# HandHeld_Terminal_V2_Rev2.net
KiCad netlist of a schematic drawn in Altium Designer
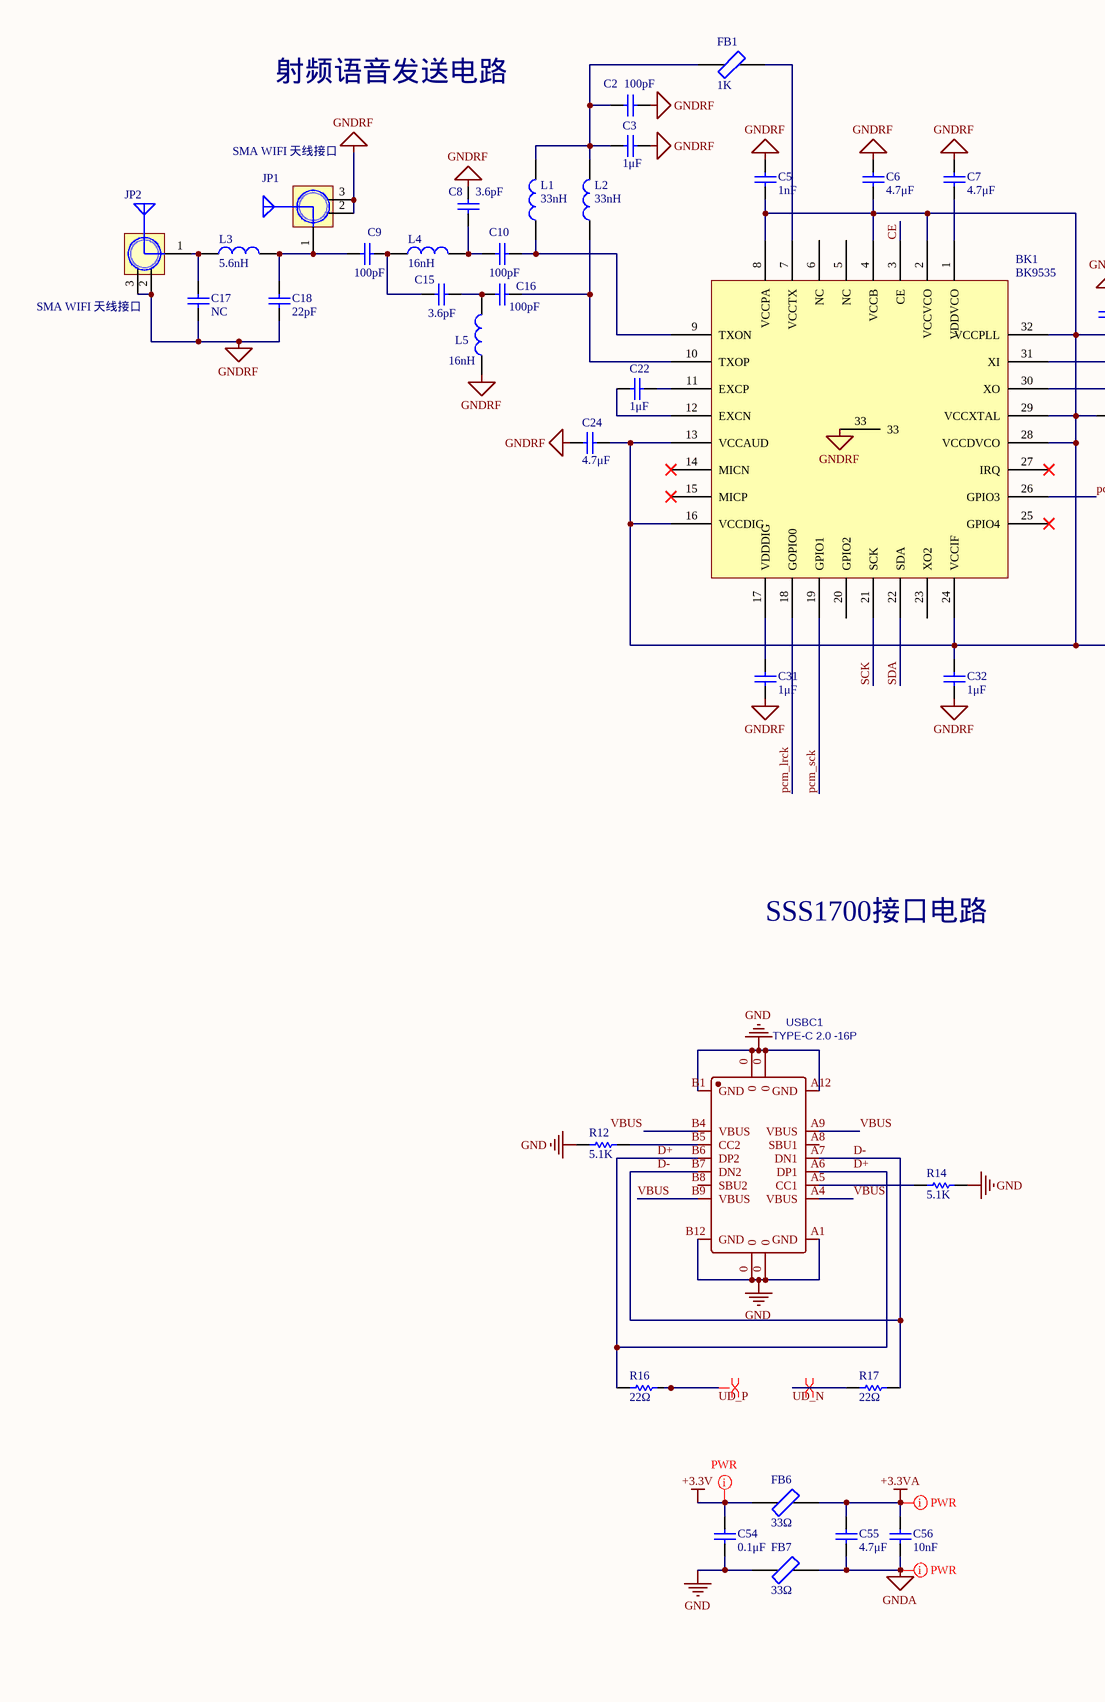
[diagram p0: HandHeld_Terminal_V2_Rev2.SchDoc, left]
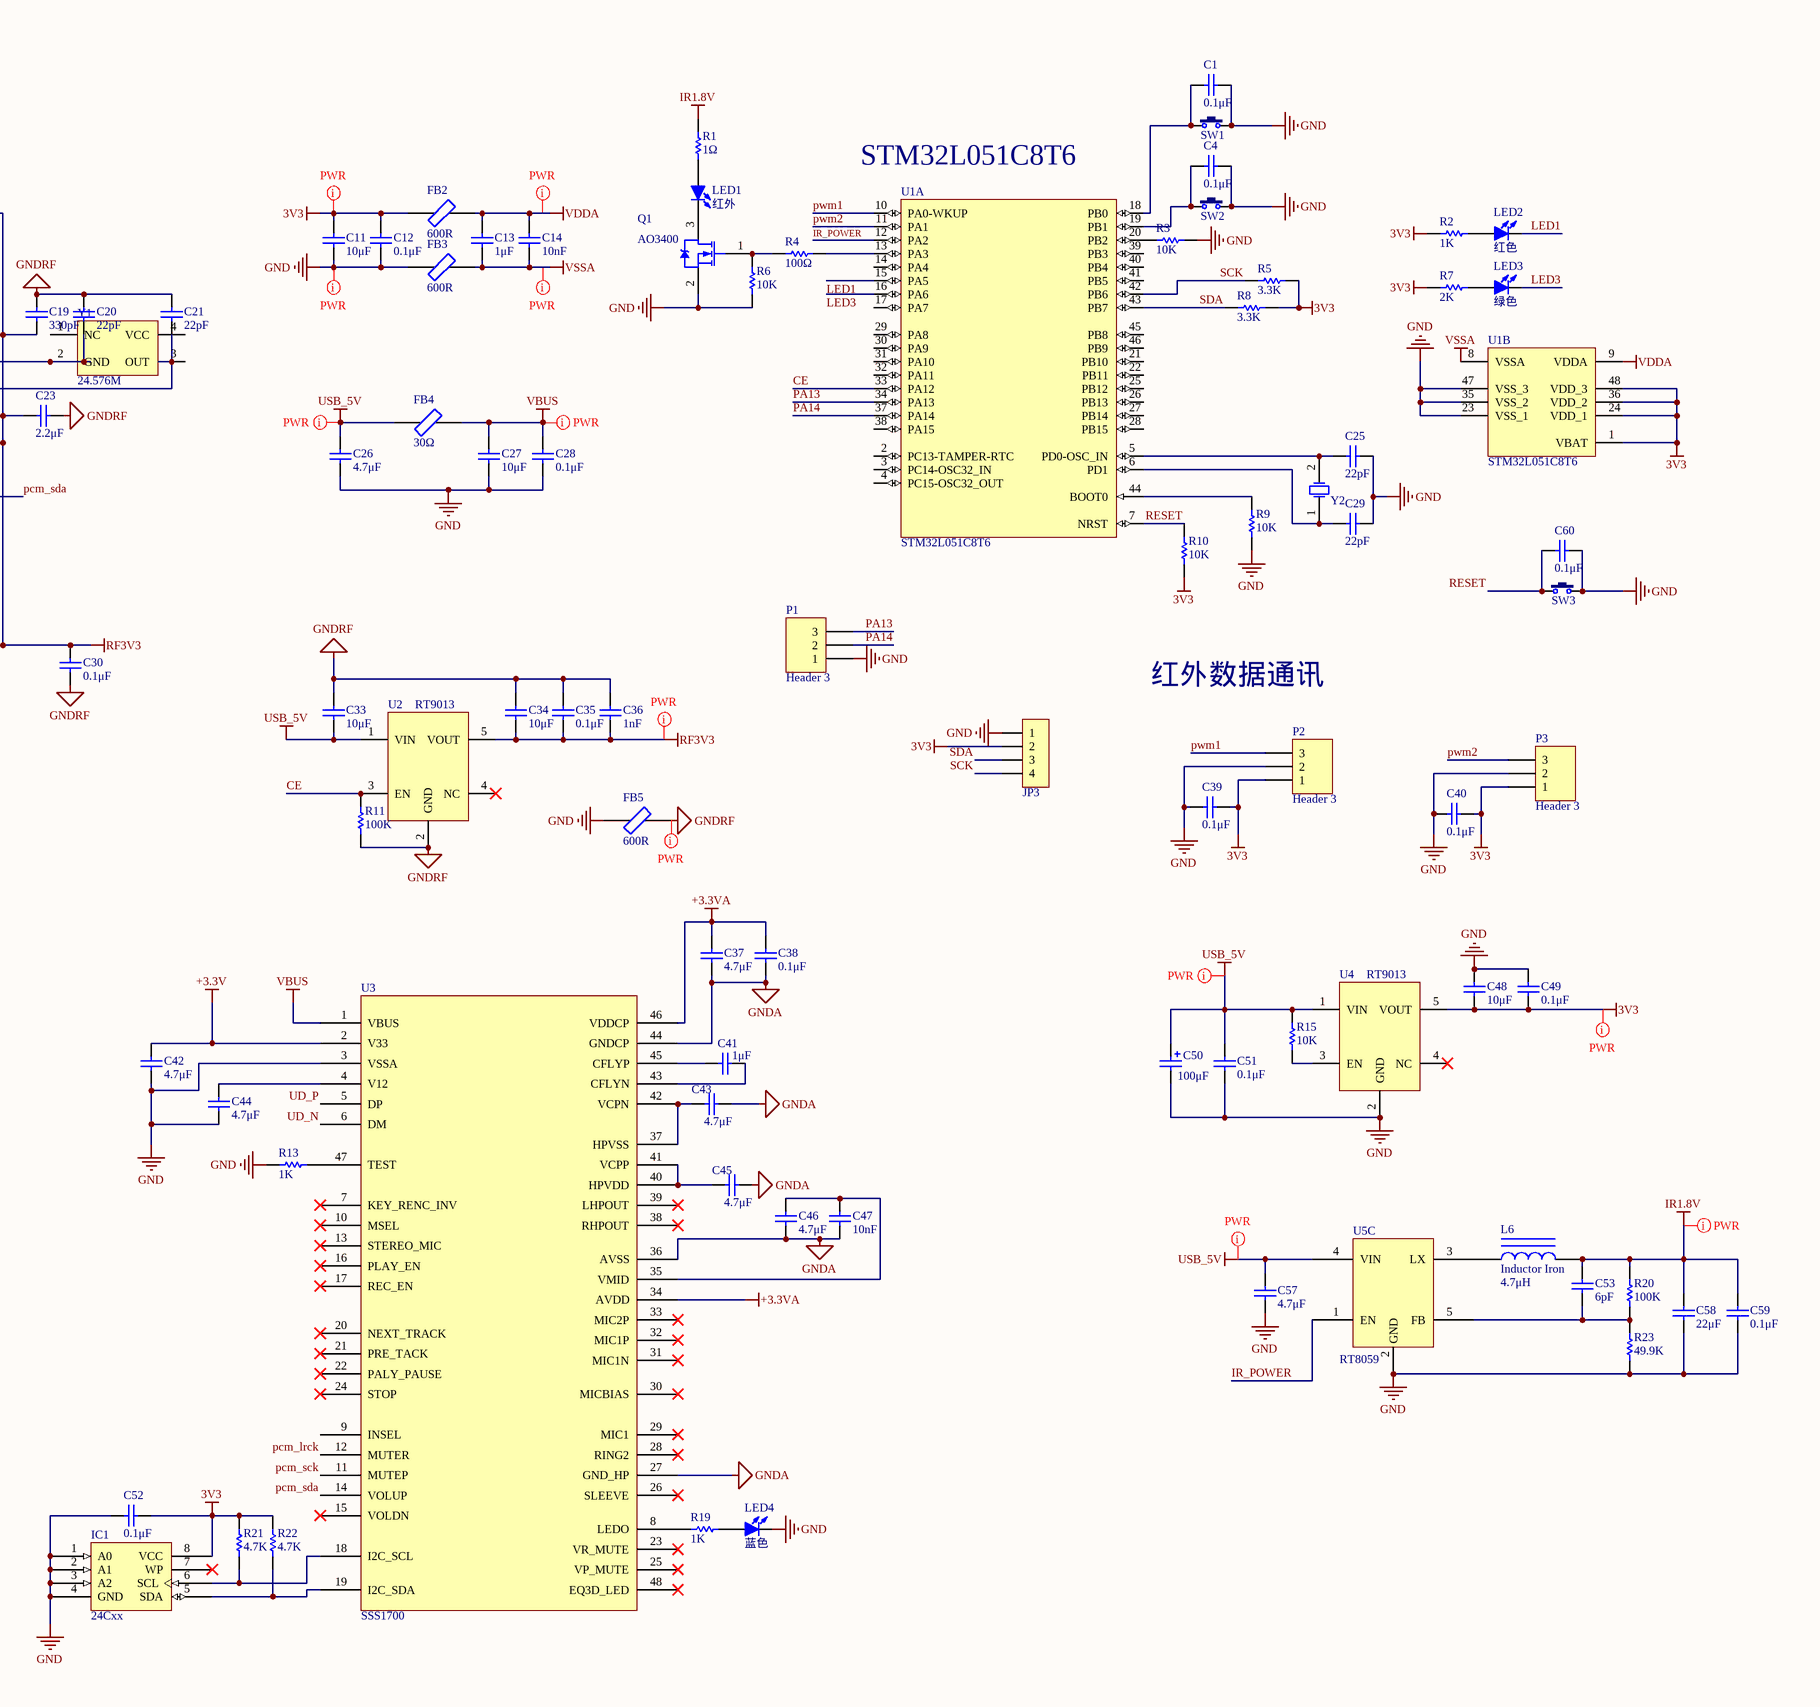
[diagram p1: HandHeld_Terminal_V2_Rev2.SchDoc, right]

(export (version "E")
  (design (tool "Eeschema 10.0.6"))
  (components
    (comp (ref "BK1") (value "BK9535") (footprint "QFN32 5x5_N") (libsource (lib "Nixie") (part "BK9530")))
    (comp (ref "C1")
      (value "0.1μF")
      (footprint "C 0603_L")
      (description "Capacitor")
      (fields (field (name "Comment") "Cap") (field (name "PUBLISHER") "Altium Limited"))
      (libsource (lib "Nixie") (part "Cap"))
    )
    (comp (ref "C2")
      (value "100pF")
      (footprint "C 0603_L")
      (description "Capacitor")
      (fields (field (name "Comment") "Cap") (field (name "PUBLISHER") "Altium Limited"))
      (libsource (lib "Nixie") (part "Cap"))
    )
    (comp (ref "C3")
      (value "1μF")
      (footprint "C 0603_L")
      (description "Capacitor")
      (fields (field (name "Comment") "Cap") (field (name "PUBLISHER") "Altium Limited"))
      (libsource (lib "Nixie") (part "Cap"))
    )
    (comp (ref "C4")
      (value "0.1μF")
      (footprint "C 0603_L")
      (description "Capacitor")
      (fields (field (name "Comment") "Cap") (field (name "PUBLISHER") "Altium Limited"))
      (libsource (lib "Nixie") (part "Cap"))
    )
    (comp (ref "C5")
      (value "1nF")
      (footprint "C 0603_L")
      (description "Capacitor")
      (fields (field (name "Comment") "Cap") (field (name "PUBLISHER") "Altium Limited"))
      (libsource (lib "Nixie") (part "Cap"))
    )
    (comp (ref "C6")
      (value "4.7μF")
      (footprint "C 0603_L")
      (description "Capacitor")
      (fields (field (name "Comment") "Cap") (field (name "PUBLISHER") "Altium Limited"))
      (libsource (lib "Nixie") (part "Cap"))
    )
    (comp (ref "C7")
      (value "4.7μF")
      (footprint "C 0603_L")
      (description "Capacitor")
      (fields (field (name "Comment") "Cap") (field (name "PUBLISHER") "Altium Limited"))
      (libsource (lib "Nixie") (part "Cap"))
    )
    (comp (ref "C8")
      (value "3.6pF")
      (footprint "C 0603_L")
      (description "Capacitor")
      (fields (field (name "Comment") "Cap") (field (name "PUBLISHER") "Altium Limited"))
      (libsource (lib "Nixie") (part "Cap"))
    )
    (comp (ref "C9")
      (value "100pF")
      (footprint "C 0603_L")
      (description "Capacitor")
      (fields (field (name "Comment") "Cap") (field (name "PUBLISHER") "Altium Limited"))
      (libsource (lib "Nixie") (part "Cap"))
    )
    (comp (ref "C10")
      (value "100pF")
      (footprint "C 0603_L")
      (description "Capacitor")
      (fields (field (name "Comment") "Cap") (field (name "PUBLISHER") "Altium Limited"))
      (libsource (lib "Nixie") (part "Cap"))
    )
    (comp (ref "C11")
      (value "10μF")
      (footprint "C 0805_L")
      (description "Capacitor")
      (fields (field (name "Comment") "Cap") (field (name "PUBLISHER") "Altium Limited"))
      (libsource (lib "Nixie") (part "Cap"))
    )
    (comp (ref "C12")
      (value "0.1μF")
      (footprint "C 0603_L")
      (description "Capacitor")
      (fields (field (name "Comment") "Cap") (field (name "PUBLISHER") "Altium Limited"))
      (libsource (lib "Nixie") (part "Cap"))
    )
    (comp (ref "C13")
      (value "1μF")
      (footprint "C 0603_L")
      (description "Capacitor")
      (fields (field (name "Comment") "Cap") (field (name "PUBLISHER") "Altium Limited"))
      (libsource (lib "Nixie") (part "Cap"))
    )
    (comp (ref "C14")
      (value "10nF")
      (footprint "C 0603_L")
      (description "Capacitor")
      (fields (field (name "Comment") "Cap") (field (name "PUBLISHER") "Altium Limited"))
      (libsource (lib "Nixie") (part "Cap"))
    )
    (comp (ref "C15")
      (value "3.6pF")
      (footprint "C 0603_L")
      (description "Capacitor")
      (fields (field (name "Comment") "Cap") (field (name "PUBLISHER") "Altium Limited"))
      (libsource (lib "Nixie") (part "Cap"))
    )
    (comp (ref "C16")
      (value "100pF")
      (footprint "C 0603_L")
      (description "Capacitor")
      (fields (field (name "Comment") "Cap") (field (name "PUBLISHER") "Altium Limited"))
      (libsource (lib "Nixie") (part "Cap"))
    )
    (comp (ref "C17")
      (value "NC")
      (footprint "C 0603_L")
      (description "Capacitor")
      (fields (field (name "Comment") "Cap") (field (name "PUBLISHER") "Altium Limited"))
      (libsource (lib "Nixie") (part "Cap"))
    )
    (comp (ref "C18")
      (value "22pF")
      (footprint "C 0603_L")
      (description "Capacitor")
      (fields (field (name "Comment") "Cap") (field (name "PUBLISHER") "Altium Limited"))
      (libsource (lib "Nixie") (part "Cap"))
    )
    (comp (ref "C19")
      (value "330pF")
      (footprint "C 0603_L")
      (description "Capacitor")
      (fields (field (name "Comment") "Cap") (field (name "PUBLISHER") "Altium Limited"))
      (libsource (lib "Nixie") (part "Cap"))
    )
    (comp (ref "C20")
      (value "22pF")
      (footprint "C 0603_L")
      (description "Capacitor")
      (fields (field (name "Comment") "Cap") (field (name "PUBLISHER") "Altium Limited"))
      (libsource (lib "Nixie") (part "Cap"))
    )
    (comp (ref "C21")
      (value "22pF")
      (footprint "C 0603_L")
      (description "Capacitor")
      (fields (field (name "Comment") "Cap") (field (name "PUBLISHER") "Altium Limited"))
      (libsource (lib "Nixie") (part "Cap"))
    )
    (comp (ref "C22")
      (value "1μF")
      (footprint "C 0603_L")
      (description "Capacitor")
      (fields (field (name "Comment") "Cap") (field (name "PUBLISHER") "Altium Limited"))
      (libsource (lib "Nixie") (part "Cap"))
    )
    (comp (ref "C23")
      (value "2.2μF")
      (footprint "C 0603_L")
      (description "Capacitor")
      (fields (field (name "Comment") "Cap") (field (name "PUBLISHER") "Altium Limited"))
      (libsource (lib "Nixie") (part "Cap"))
    )
    (comp (ref "C24")
      (value "4.7μF")
      (footprint "C 0603_L")
      (description "Capacitor")
      (fields (field (name "Comment") "Cap") (field (name "PUBLISHER") "Altium Limited"))
      (libsource (lib "Nixie") (part "Cap"))
    )
    (comp (ref "C25")
      (value "22pF")
      (footprint "C 0603_L")
      (description "Capacitor")
      (fields (field (name "Comment") "Cap") (field (name "PUBLISHER") "Altium Limited"))
      (libsource (lib "Nixie") (part "Cap"))
    )
    (comp (ref "C26")
      (value "4.7μF")
      (footprint "C 0805_L")
      (description "Capacitor")
      (fields (field (name "Comment") "Cap") (field (name "PUBLISHER") "Altium Limited"))
      (libsource (lib "Nixie") (part "Cap"))
    )
    (comp (ref "C27")
      (value "10μF")
      (footprint "C 0805_L")
      (description "Capacitor")
      (fields (field (name "Comment") "Cap") (field (name "PUBLISHER") "Altium Limited"))
      (libsource (lib "Nixie") (part "Cap"))
    )
    (comp (ref "C28")
      (value "0.1μF")
      (footprint "C 0603_L")
      (description "Capacitor")
      (fields (field (name "Comment") "Cap") (field (name "PUBLISHER") "Altium Limited"))
      (libsource (lib "Nixie") (part "Cap"))
    )
    (comp (ref "C29")
      (value "22pF")
      (footprint "C 0603_L")
      (description "Capacitor")
      (fields (field (name "Comment") "Cap") (field (name "PUBLISHER") "Altium Limited"))
      (libsource (lib "Nixie") (part "Cap"))
    )
    (comp (ref "C30")
      (value "0.1μF")
      (footprint "C 0603_L")
      (description "Capacitor")
      (fields (field (name "Comment") "Cap") (field (name "PUBLISHER") "Altium Limited"))
      (libsource (lib "Nixie") (part "Cap"))
    )
    (comp (ref "C31")
      (value "1μF")
      (footprint "C 0603_L")
      (description "Capacitor")
      (fields (field (name "Comment") "Cap") (field (name "PUBLISHER") "Altium Limited"))
      (libsource (lib "Nixie") (part "Cap"))
    )
    (comp (ref "C32")
      (value "1μF")
      (footprint "C 0603_L")
      (description "Capacitor")
      (fields (field (name "Comment") "Cap") (field (name "PUBLISHER") "Altium Limited"))
      (libsource (lib "Nixie") (part "Cap"))
    )
    (comp (ref "C33")
      (value "10μF")
      (footprint "C 0805_L")
      (description "Capacitor")
      (fields (field (name "Comment") "Cap") (field (name "PUBLISHER") "Altium Limited"))
      (libsource (lib "Nixie") (part "Cap"))
    )
    (comp (ref "C34")
      (value "10μF")
      (footprint "C 0805_L")
      (description "Capacitor")
      (fields (field (name "Comment") "Cap") (field (name "PUBLISHER") "Altium Limited"))
      (libsource (lib "Nixie") (part "Cap"))
    )
    (comp (ref "C35")
      (value "0.1μF")
      (footprint "C 0603_L")
      (description "Capacitor")
      (fields (field (name "Comment") "Cap") (field (name "PUBLISHER") "Altium Limited"))
      (libsource (lib "Nixie") (part "Cap"))
    )
    (comp (ref "C36")
      (value "1nF")
      (footprint "C 0603_L")
      (description "Capacitor")
      (fields (field (name "Comment") "Cap") (field (name "PUBLISHER") "Altium Limited"))
      (libsource (lib "Nixie") (part "Cap"))
    )
    (comp (ref "C37")
      (value "4.7μF")
      (footprint "C 0603_L")
      (description "Capacitor")
      (fields (field (name "Comment") "Cap") (field (name "PUBLISHER") "Altium Limited"))
      (libsource (lib "Nixie") (part "Cap"))
    )
    (comp (ref "C38")
      (value "0.1μF")
      (footprint "C 0603_L")
      (description "Capacitor")
      (fields (field (name "Comment") "Cap") (field (name "PUBLISHER") "Altium Limited"))
      (libsource (lib "Nixie") (part "Cap"))
    )
    (comp (ref "C39")
      (value "0.1μF")
      (footprint "C 0603_L")
      (description "Capacitor")
      (fields (field (name "Comment") "Cap") (field (name "PUBLISHER") "Altium Limited"))
      (libsource (lib "Nixie") (part "Cap"))
    )
    (comp (ref "C40")
      (value "0.1μF")
      (footprint "C 0603_L")
      (description "Capacitor")
      (fields (field (name "Comment") "Cap") (field (name "PUBLISHER") "Altium Limited"))
      (libsource (lib "Nixie") (part "Cap"))
    )
    (comp (ref "C41")
      (value "1μF")
      (footprint "C 0603_L")
      (description "Capacitor")
      (fields (field (name "Comment") "Cap") (field (name "PUBLISHER") "Altium Limited"))
      (libsource (lib "Nixie") (part "Cap"))
    )
    (comp (ref "C42")
      (value "4.7μF")
      (footprint "C 0603_L")
      (description "Capacitor")
      (fields (field (name "Comment") "Cap") (field (name "PUBLISHER") "Altium Limited"))
      (libsource (lib "Nixie") (part "Cap"))
    )
    (comp (ref "C43")
      (value "4.7μF")
      (footprint "C 0603_L")
      (description "Capacitor")
      (fields (field (name "Comment") "Cap") (field (name "PUBLISHER") "Altium Limited"))
      (libsource (lib "Nixie") (part "Cap"))
    )
    (comp (ref "C44")
      (value "4.7μF")
      (footprint "C 0603_L")
      (description "Capacitor")
      (fields (field (name "Comment") "Cap") (field (name "PUBLISHER") "Altium Limited"))
      (libsource (lib "Nixie") (part "Cap"))
    )
    (comp (ref "C45")
      (value "4.7μF")
      (footprint "C 0603_L")
      (description "Capacitor")
      (fields (field (name "Comment") "Cap") (field (name "PUBLISHER") "Altium Limited"))
      (libsource (lib "Nixie") (part "Cap"))
    )
    (comp (ref "C46")
      (value "4.7μF")
      (footprint "C 0603_L")
      (description "Capacitor")
      (fields (field (name "Comment") "Cap") (field (name "PUBLISHER") "Altium Limited"))
      (libsource (lib "Nixie") (part "Cap"))
    )
    (comp (ref "C47")
      (value "10nF")
      (footprint "C 0603_L")
      (description "Capacitor")
      (fields (field (name "Comment") "Cap") (field (name "PUBLISHER") "Altium Limited"))
      (libsource (lib "Nixie") (part "Cap"))
    )
    (comp (ref "C48")
      (value "10μF")
      (footprint "C 0805_L")
      (description "Capacitor")
      (fields (field (name "Comment") "Cap") (field (name "PUBLISHER") "Altium Limited"))
      (libsource (lib "Nixie") (part "Cap"))
    )
    (comp (ref "C49")
      (value "0.1μF")
      (footprint "C 0603_L")
      (description "Capacitor")
      (fields (field (name "Comment") "Cap") (field (name "PUBLISHER") "Altium Limited"))
      (libsource (lib "Nixie") (part "Cap"))
    )
    (comp (ref "C50")
      (value "100μF")
      (footprint "CM C(5*5.4)")
      (description "Polarized Capacitor (Radial)")
      (fields (field (name "Comment") "Cap Pol1") (field (name "PUBLISHER") "Altium Limited"))
      (libsource (lib "Nixie") (part "Cap Pol1"))
    )
    (comp (ref "C51")
      (value "0.1μF")
      (footprint "C 0603_L")
      (description "Capacitor")
      (fields (field (name "Comment") "Cap") (field (name "PUBLISHER") "Altium Limited"))
      (libsource (lib "Nixie") (part "Cap"))
    )
    (comp (ref "C52")
      (value "0.1μF")
      (footprint "C 0603_L")
      (description "Capacitor")
      (fields (field (name "Comment") "Cap") (field (name "PUBLISHER") "Altium Limited"))
      (libsource (lib "Nixie") (part "Cap"))
    )
    (comp (ref "C53")
      (value "6pF")
      (footprint "C 0603_L")
      (description "Capacitor")
      (fields (field (name "Comment") "Cap") (field (name "PUBLISHER") "Altium Limited"))
      (libsource (lib "Nixie") (part "Cap"))
    )
    (comp (ref "C54")
      (value "0.1μF")
      (footprint "C 0603_L")
      (description "Capacitor")
      (fields (field (name "Comment") "Cap") (field (name "PUBLISHER") "Altium Limited"))
      (libsource (lib "Nixie") (part "Cap"))
    )
    (comp (ref "C55")
      (value "4.7μF")
      (footprint "C 0805_L")
      (description "Capacitor")
      (fields (field (name "Comment") "Cap") (field (name "PUBLISHER") "Altium Limited"))
      (libsource (lib "Nixie") (part "Cap"))
    )
    (comp (ref "C56")
      (value "10nF")
      (footprint "C 0603_L")
      (description "Capacitor")
      (fields (field (name "Comment") "Cap") (field (name "PUBLISHER") "Altium Limited"))
      (libsource (lib "Nixie") (part "Cap"))
    )
    (comp (ref "C57")
      (value "4.7μF")
      (footprint "C 0603_L")
      (description "Capacitor")
      (fields (field (name "Comment") "Cap") (field (name "PUBLISHER") "Altium Limited"))
      (libsource (lib "Nixie") (part "Cap"))
    )
    (comp (ref "C58")
      (value "22μF")
      (footprint "C 0805_L")
      (description "Capacitor")
      (fields (field (name "Comment") "Cap") (field (name "PUBLISHER") "Altium Limited"))
      (libsource (lib "Nixie") (part "Cap"))
    )
    (comp (ref "C59")
      (value "0.1μF")
      (footprint "C 0603_L")
      (description "Capacitor")
      (fields (field (name "Comment") "Cap") (field (name "PUBLISHER") "Altium Limited"))
      (libsource (lib "Nixie") (part "Cap"))
    )
    (comp (ref "C60")
      (value "0.1μF")
      (footprint "C 0603_L")
      (description "Capacitor")
      (fields (field (name "Comment") "Cap") (field (name "PUBLISHER") "Altium Limited"))
      (libsource (lib "Nixie") (part "Cap"))
    )
    (comp (ref "FB1")
      (value "1K")
      (footprint "C 0603_L")
      (description "铁氧体磁珠")
      (fields (field (name "Comment") "Ferrite bead"))
      (libsource (lib "Nixie") (part "Ferrite bead"))
    )
    (comp (ref "FB2")
      (value "600R")
      (footprint "C 0603_L")
      (description "铁氧体磁珠")
      (fields (field (name "Comment") "Ferrite bead"))
      (libsource (lib "Nixie") (part "Ferrite bead"))
    )
    (comp (ref "FB3")
      (value "600R")
      (footprint "C 0603_L")
      (description "铁氧体磁珠")
      (fields (field (name "Comment") "Ferrite bead"))
      (libsource (lib "Nixie") (part "Ferrite bead"))
    )
    (comp (ref "FB4")
      (value "30Ω")
      (footprint "C 0603_L")
      (description "铁氧体磁珠")
      (fields (field (name "Comment") "Ferrite bead"))
      (libsource (lib "Nixie") (part "Ferrite bead"))
    )
    (comp (ref "FB5")
      (value "600R")
      (footprint "C 0805_L")
      (description "铁氧体磁珠")
      (fields (field (name "Comment") "Ferrite bead"))
      (libsource (lib "Nixie") (part "Ferrite bead"))
    )
    (comp (ref "FB6")
      (value "33Ω")
      (footprint "C 0603_L")
      (description "铁氧体磁珠")
      (fields (field (name "Comment") "Ferrite bead"))
      (libsource (lib "Nixie") (part "Ferrite bead"))
    )
    (comp (ref "FB7")
      (value "33Ω")
      (footprint "C 0603_L")
      (description "铁氧体磁珠")
      (fields (field (name "Comment") "Ferrite bead"))
      (libsource (lib "Nixie") (part "Ferrite bead"))
    )
    (comp (ref "IC1")
      (value "24Cxx")
      (footprint "SOP8_L")
      (description "外置EEPROM")
      (fields (field (name "版权归属") "封装库来自淘宝 ID：黄晶宝石"))
      (libsource (lib "Nixie") (part "24Cxx"))
    )
    (comp (ref "JP1")
      (value "SMA WIFI 天线接口")
      (footprint "COAXIAL/SMD/CON/V/I-PEX/W08-5801")
      (description "SMA-2.4G射频天线接口")
      (fields (field (name "版权归属") "封装库来自淘宝 ID：黄晶宝石"))
      (libsource (lib "") (part "SMA_1"))
    )
    (comp (ref "JP2")
      (value "SMA WIFI 天线接口")
      (footprint "SMA-KE")
      (description "SMA-2.4G射频天线接口")
      (fields (field (name "版权归属") "封装库来自淘宝 ID：黄晶宝石"))
      (libsource (lib "Nixie") (part "SMA"))
    )
    (comp (ref "JP3")
      (value "HDR-1X4")
      (footprint "HDR2.54-LI-4P")
      (description "4P接插件")
      (fields (field (name "版权归属") "封装库来自淘宝 ID：黄晶宝石"))
      (libsource (lib "Nixie") (part "Header 4"))
    )
    (comp (ref "L1")
      (value "33nH")
      (footprint "L 0603")
      (description "小功率贴片电感")
      (fields (field (name "Comment") "L"))
      (libsource (lib "Nixie") (part "L"))
    )
    (comp (ref "L2")
      (value "33nH")
      (footprint "L 0603")
      (description "小功率贴片电感")
      (fields (field (name "Comment") "L"))
      (libsource (lib "Nixie") (part "L"))
    )
    (comp (ref "L3")
      (value "5.6nH")
      (footprint "L 0603")
      (description "小功率贴片电感")
      (fields (field (name "Comment") "L"))
      (libsource (lib "Nixie") (part "L"))
    )
    (comp (ref "L4")
      (value "16nH")
      (footprint "L 0603")
      (description "小功率贴片电感")
      (fields (field (name "Comment") "L"))
      (libsource (lib "Nixie") (part "L"))
    )
    (comp (ref "L5")
      (value "16nH")
      (footprint "L 0603")
      (description "小功率贴片电感")
      (fields (field (name "Comment") "L"))
      (libsource (lib "Nixie") (part "L"))
    )
    (comp (ref "L6")
      (value "Inductor Iron")
      (footprint "NR2520")
      (description "Magnetic-Core Inductor")
      (fields (field (name "ALTIUM_VALUE") "4.7μH") (field (name "PUBLISHER") "Altium Limited"))
      (libsource (lib "Nixie") (part "Inductor Iron"))
    )
    (comp (ref "LED1")
      (value "红外")
      (footprint "LED 1W/3W")
      (description "贴片LED")
      (fields (field (name "版权归属") "封装库来自淘宝 ID：黄晶宝石"))
      (libsource (lib "Nixie") (part "LED-SMD"))
    )
    (comp (ref "LED2")
      (value "红色")
      (footprint "LED 0805R")
      (description "贴片LED")
      (fields (field (name "版权归属") "封装库来自淘宝 ID：黄晶宝石"))
      (libsource (lib "Nixie") (part "LED-SMD"))
    )
    (comp (ref "LED3")
      (value "绿色")
      (footprint "LED 0805G")
      (description "贴片LED")
      (fields (field (name "版权归属") "封装库来自淘宝 ID：黄晶宝石"))
      (libsource (lib "Nixie") (part "LED-SMD"))
    )
    (comp (ref "LED4")
      (value "蓝色")
      (footprint "LED 0805B")
      (description "贴片LED")
      (fields (field (name "版权归属") "封装库来自淘宝 ID：黄晶宝石"))
      (libsource (lib "Nixie") (part "LED-SMD"))
    )
    (comp (ref "P1")
      (value "Header 3")
      (footprint "HDR2.54-LI-3P")
      (description "Header, 3-Pin")
      (fields (field (name "PUBLISHER") "Altium Limited"))
      (libsource (lib "Miscellaneous Connectors") (part "Header 3"))
    )
    (comp (ref "P2")
      (value "Header 3")
      (footprint "HDR1X3")
      (description "Header, 3-Pin")
      (fields (field (name "PUBLISHER") "Altium Limited"))
      (libsource (lib "") (part "Header 3_1"))
    )
    (comp (ref "P3")
      (value "Header 3")
      (footprint "HDR1X3")
      (description "Header, 3-Pin")
      (fields (field (name "PUBLISHER") "Altium Limited"))
      (libsource (lib "") (part "Header 3_1"))
    )
    (comp (ref "Q1")
      (value "AO3400")
      (footprint "SOT-23-3L")
      (description "N-Channel Power MOSFET")
      (fields (field (name "PUBLISHER") "Altium Limited"))
      (libsource (lib "Nixie") (part "NMOS-2"))
    )
    (comp (ref "R1")
      (value "1Ω")
      (footprint "R 0805_L")
      (description "Resistor")
      (fields (field (name "PUBLISHER") "Altium Limited"))
      (libsource (lib "Nixie") (part "Resistor"))
    )
    (comp (ref "R2")
      (value "1K")
      (footprint "R 0603_L")
      (description "Resistor")
      (fields (field (name "PUBLISHER") "Altium Limited"))
      (libsource (lib "Nixie") (part "Resistor"))
    )
    (comp (ref "R3")
      (value "10K")
      (footprint "R 0603_L")
      (description "Resistor")
      (fields (field (name "PUBLISHER") "Altium Limited"))
      (libsource (lib "Nixie") (part "Resistor"))
    )
    (comp (ref "R4")
      (value "100Ω")
      (footprint "R 0603_L")
      (description "Resistor")
      (fields (field (name "PUBLISHER") "Altium Limited"))
      (libsource (lib "Nixie") (part "Resistor"))
    )
    (comp (ref "R5")
      (value "3.3K")
      (footprint "R 0603_L")
      (description "Resistor")
      (fields (field (name "PUBLISHER") "Altium Limited"))
      (libsource (lib "Nixie") (part "Resistor"))
    )
    (comp (ref "R6")
      (value "10K")
      (footprint "R 0603_L")
      (description "Resistor")
      (fields (field (name "PUBLISHER") "Altium Limited"))
      (libsource (lib "Nixie") (part "Resistor"))
    )
    (comp (ref "R7")
      (value "2K")
      (footprint "R 0603_L")
      (description "Resistor")
      (fields (field (name "PUBLISHER") "Altium Limited"))
      (libsource (lib "Nixie") (part "Resistor"))
    )
    (comp (ref "R8")
      (value "3.3K")
      (footprint "R 0603_L")
      (description "Resistor")
      (fields (field (name "PUBLISHER") "Altium Limited"))
      (libsource (lib "Nixie") (part "Resistor"))
    )
    (comp (ref "R9")
      (value "10K")
      (footprint "R 0603_L")
      (description "Resistor")
      (fields (field (name "PUBLISHER") "Altium Limited"))
      (libsource (lib "Nixie") (part "Resistor"))
    )
    (comp (ref "R10")
      (value "10K")
      (footprint "R 0603_L")
      (description "Resistor")
      (fields (field (name "PUBLISHER") "Altium Limited"))
      (libsource (lib "Nixie") (part "Resistor"))
    )
    (comp (ref "R11")
      (value "100K")
      (footprint "R 0603_L")
      (description "Resistor")
      (fields (field (name "PUBLISHER") "Altium Limited"))
      (libsource (lib "Nixie") (part "Resistor"))
    )
    (comp (ref "R12")
      (value "5.1K")
      (footprint "R 0603_L")
      (description "Resistor")
      (fields (field (name "PUBLISHER") "Altium Limited"))
      (libsource (lib "Nixie") (part "Resistor"))
    )
    (comp (ref "R13")
      (value "1K")
      (footprint "R 0603_L")
      (description "Resistor")
      (fields (field (name "PUBLISHER") "Altium Limited"))
      (libsource (lib "Nixie") (part "Resistor"))
    )
    (comp (ref "R14")
      (value "5.1K")
      (footprint "R 0603_L")
      (description "Resistor")
      (fields (field (name "PUBLISHER") "Altium Limited"))
      (libsource (lib "Nixie") (part "Resistor"))
    )
    (comp (ref "R15")
      (value "10K")
      (footprint "R 0603_L")
      (description "Resistor")
      (fields (field (name "PUBLISHER") "Altium Limited"))
      (libsource (lib "Nixie") (part "Resistor"))
    )
    (comp (ref "R16")
      (value "22Ω")
      (footprint "R 0603_L")
      (description "Resistor")
      (fields (field (name "PUBLISHER") "Altium Limited"))
      (libsource (lib "Nixie") (part "Resistor"))
    )
    (comp (ref "R17")
      (value "22Ω")
      (footprint "R 0603_L")
      (description "Resistor")
      (fields (field (name "PUBLISHER") "Altium Limited"))
      (libsource (lib "Nixie") (part "Resistor"))
    )
    (comp (ref "R19")
      (value "1K")
      (footprint "R 0603_L")
      (description "Resistor")
      (fields (field (name "PUBLISHER") "Altium Limited"))
      (libsource (lib "Nixie") (part "Resistor"))
    )
    (comp (ref "R20")
      (value "100K")
      (footprint "R 0603_L")
      (description "Resistor")
      (fields (field (name "PUBLISHER") "Altium Limited"))
      (libsource (lib "Nixie") (part "Resistor"))
    )
    (comp (ref "R21")
      (value "4.7K")
      (footprint "R 0603_L")
      (description "Resistor")
      (fields (field (name "PUBLISHER") "Altium Limited"))
      (libsource (lib "Nixie") (part "Resistor"))
    )
    (comp (ref "R22")
      (value "4.7K")
      (footprint "R 0603_L")
      (description "Resistor")
      (fields (field (name "PUBLISHER") "Altium Limited"))
      (libsource (lib "Nixie") (part "Resistor"))
    )
    (comp (ref "R23")
      (value "49.9K")
      (footprint "R 0603_L")
      (description "Resistor")
      (fields (field (name "PUBLISHER") "Altium Limited"))
      (libsource (lib "Nixie") (part "Resistor"))
    )
    (comp (ref "SW1")
      (value "3x6x5")
      (footprint "TSW SMD-3*6*2.5")
      (description "3x6轻触开关")
      (fields (field (name "版权归属") "封装库来自淘宝 ID：黄晶宝石"))
      (libsource (lib "Nixie") (part "TSW 3x6"))
    )
    (comp (ref "SW2")
      (value "3x6x5")
      (footprint "TSW SMD-3*6*2.5")
      (description "3x6轻触开关")
      (fields (field (name "版权归属") "封装库来自淘宝 ID：黄晶宝石"))
      (libsource (lib "Nixie") (part "TSW 3x6"))
    )
    (comp (ref "SW3")
      (value "3x6x5")
      (footprint "TSW SMD-3*6*2.5")
      (description "3x6轻触开关")
      (fields (field (name "版权归属") "封装库来自淘宝 ID：黄晶宝石"))
      (libsource (lib "Nixie") (part "TSW 3x6"))
    )
    (comp (ref "U1")
      (value "STM32L051C8T6")
      (footprint "LQFP48_L")
      (description "ARM")
      (libsource (lib "") (part "STM32F103C8T6_1"))
    )
    (comp (ref "U2")
      (value "RT9013")
      (footprint "SOT23-5L")
      (description "LDO")
      (libsource (lib "HandHeld_terminal") (part "RT9013"))
    )
    (comp (ref "U3")
      (value "SSS1700")
      (footprint "LQFP48_L")
      (description "USB音频芯片")
      (libsource (lib "Nixie") (part "SSS1700"))
    )
    (comp (ref "U4")
      (value "RT9013")
      (footprint "SOT23-5L")
      (description "LDO")
      (libsource (lib "HandHeld_terminal") (part "RT9013"))
    )
    (comp (ref "U5")
      (value "RT8059")
      (footprint "SOT23-5L")
      (description "DC-DC, 2.8-5.5V,1A")
      (libsource (lib "Nixie") (part "RT8059"))
    )
    (comp (ref "USBC1")
      (value "TYPE-C 2.0 -16P")
      (footprint "USB-C-SMD_TYPE-C-USB-5")
      (description "USB2.0 Type-C 母座 16Pin")
      (libsource (lib "Nixie") (part "USB2.0 Type-C 16Pin母座"))
    )
    (comp (ref "Y1")
      (value "24.576M")
      (footprint "OSC 3225-4P")
      (description "4脚有源晶振")
      (libsource (lib "Nixie") (part "XTAL"))
    )
    (comp (ref "Y2")
      (value "8MHz ±20ppm 20pF")
      (footprint "OSC 5032-2P")
      (description "贴片晶振")
      (libsource (lib "HandHeld_terminal") (part "SMD-5032_2P 8MHz 20ppm 20pF"))
    )
  )
  (nets
    (net (code "1") (name "+3.3V") (class "Default")
      (node (ref "C42") (pin "2") (pinfunction "2_2") (pintype "passive"))
      (node (ref "C54") (pin "2") (pinfunction "2_2") (pintype "passive"))
      (node (ref "FB6") (pin "1") (pinfunction "1_1") (pintype "passive"))
      (node (ref "U3") (pin "2") (pinfunction "V33_2") (pintype "passive"))
    )
    (net (code "2") (name "+3.3VA") (class "Default")
      (node (ref "C37") (pin "2") (pinfunction "2_2") (pintype "passive"))
      (node (ref "C38") (pin "2") (pinfunction "2_2") (pintype "passive"))
      (node (ref "C55") (pin "2") (pinfunction "2_2") (pintype "passive"))
      (node (ref "C56") (pin "2") (pinfunction "2_2") (pintype "passive"))
      (node (ref "FB6") (pin "2") (pinfunction "2_2") (pintype "passive"))
      (node (ref "U3") (pin "34") (pinfunction "AVDD_34") (pintype "passive"))
      (node (ref "U3") (pin "46") (pinfunction "VDDCP_46") (pintype "passive"))
    )
    (net (code "3") (name "/CE") (class "Default")
      (node (ref "BK1") (pin "3") (pinfunction "CE_3") (pintype "passive"))
      (node (ref "R11") (pin "2") (pinfunction "2_2") (pintype "passive"))
      (node (ref "U1") (pin "33") (pinfunction "PA12_33") (pintype "bidirectional"))
      (node (ref "U2") (pin "3") (pinfunction "EN_3") (pintype "passive"))
    )
    (net (code "4") (name "/D+") (class "Default")
      (node (ref "R16") (pin "1") (pinfunction "1_1") (pintype "passive"))
      (node (ref "USBC1") (pin "A6") (pinfunction "DP1_A6") (pintype "passive"))
      (node (ref "USBC1") (pin "B6") (pinfunction "DP2_B6") (pintype "passive"))
    )
    (net (code "5") (name "/D-") (class "Default")
      (node (ref "R17") (pin "2") (pinfunction "2_2") (pintype "passive"))
      (node (ref "USBC1") (pin "A7") (pinfunction "DN1_A7") (pintype "passive"))
      (node (ref "USBC1") (pin "B7") (pinfunction "DN2_B7") (pintype "passive"))
    )
    (net (code "6") (name "/IR_POWER") (class "Default")
      (node (ref "U1") (pin "12") (pinfunction "PA2_12") (pintype "bidirectional"))
      (node (ref "U5") (pin "1") (pinfunction "EN_1") (pintype "passive"))
    )
    (net (code "7") (name "/LED1") (class "Default")
      (node (ref "LED2") (pin "2") (pinfunction "K_2") (pintype "passive"))
      (node (ref "U1") (pin "15") (pinfunction "PA5_15") (pintype "bidirectional"))
    )
    (net (code "8") (name "/LED3") (class "Default")
      (node (ref "LED3") (pin "2") (pinfunction "K_2") (pintype "passive"))
      (node (ref "U1") (pin "16") (pinfunction "PA6_16") (pintype "bidirectional"))
    )
    (net (code "9") (name "/PA13") (class "Default")
      (node (ref "P1") (pin "3") (pinfunction "3_3") (pintype "passive"))
      (node (ref "U1") (pin "34") (pinfunction "PA13_34") (pintype "bidirectional"))
    )
    (net (code "10") (name "/PA14") (class "Default")
      (node (ref "P1") (pin "2") (pinfunction "2_2") (pintype "passive"))
      (node (ref "U1") (pin "37") (pinfunction "PA14_37") (pintype "bidirectional"))
    )
    (net (code "11") (name "/RESET") (class "Default")
      (node (ref "C60") (pin "2") (pinfunction "2_2") (pintype "passive"))
      (node (ref "R10") (pin "1") (pinfunction "1_1") (pintype "passive"))
      (node (ref "SW3") (pin "1") (pinfunction "1_1") (pintype "passive"))
      (node (ref "U1") (pin "7") (pinfunction "NRST_7") (pintype "bidirectional"))
    )
    (net (code "12") (name "/SCK") (class "Default")
      (node (ref "BK1") (pin "21") (pinfunction "SCK_21") (pintype "passive"))
      (node (ref "JP3") (pin "4") (pinfunction "4_4") (pintype "passive"))
      (node (ref "R5") (pin "2") (pinfunction "2_2") (pintype "passive"))
      (node (ref "U1") (pin "42") (pinfunction "PB6_42") (pintype "bidirectional"))
    )
    (net (code "13") (name "/SDA") (class "Default")
      (node (ref "BK1") (pin "22") (pinfunction "SDA_22") (pintype "passive"))
      (node (ref "JP3") (pin "3") (pinfunction "3_3") (pintype "passive"))
      (node (ref "R8") (pin "2") (pinfunction "2_2") (pintype "passive"))
      (node (ref "U1") (pin "43") (pinfunction "PB7_43") (pintype "bidirectional"))
    )
    (net (code "14") (name "/UD_N") (class "Default")
      (node (ref "R17") (pin "1") (pinfunction "1_1") (pintype "passive"))
      (node (ref "U3") (pin "6") (pinfunction "DM_6") (pintype "passive"))
    )
    (net (code "15") (name "/UD_P") (class "Default")
      (node (ref "R16") (pin "2") (pinfunction "2_2") (pintype "passive"))
      (node (ref "U3") (pin "5") (pinfunction "DP_5") (pintype "passive"))
    )
    (net (code "16") (name "/pcm_lrck") (class "Default")
      (node (ref "BK1") (pin "18") (pinfunction "GOPIO0_18") (pintype "passive"))
      (node (ref "U3") (pin "12") (pinfunction "MUTER_12") (pintype "passive"))
    )
    (net (code "17") (name "/pcm_sck") (class "Default")
      (node (ref "BK1") (pin "19") (pinfunction "GPIO1_19") (pintype "passive"))
      (node (ref "U3") (pin "11") (pinfunction "MUTEP_11") (pintype "passive"))
    )
    (net (code "18") (name "/pcm_sda") (class "Default")
      (node (ref "BK1") (pin "26") (pinfunction "GPIO3_26") (pintype "passive"))
      (node (ref "U3") (pin "14") (pinfunction "VOLUP_14") (pintype "passive"))
    )
    (net (code "19") (name "/pwm1") (class "Default")
      (node (ref "P2") (pin "3") (pinfunction "3_3") (pintype "passive"))
      (node (ref "U1") (pin "10") (pinfunction "PA0-WKUP_10") (pintype "bidirectional"))
    )
    (net (code "20") (name "/pwm2") (class "Default")
      (node (ref "P3") (pin "3") (pinfunction "3_3") (pintype "passive"))
      (node (ref "U1") (pin "11") (pinfunction "PA1_11") (pintype "bidirectional"))
    )
    (net (code "21") (name "3V3") (class "Default")
      (node (ref "C11") (pin "2") (pinfunction "2_2") (pintype "passive"))
      (node (ref "C12") (pin "2") (pinfunction "2_2") (pintype "passive"))
      (node (ref "C39") (pin "1") (pinfunction "1_1") (pintype "passive"))
      (node (ref "C40") (pin "1") (pinfunction "1_1") (pintype "passive"))
      (node (ref "C48") (pin "1") (pinfunction "1_1") (pintype "passive"))
      (node (ref "C49") (pin "2") (pinfunction "2_2") (pintype "passive"))
      (node (ref "C52") (pin "1") (pinfunction "1_1") (pintype "passive"))
      (node (ref "FB2") (pin "1") (pinfunction "1_1") (pintype "passive"))
      (node (ref "IC1") (pin "8") (pinfunction "VCC_8") (pintype "power_in"))
      (node (ref "JP3") (pin "2") (pinfunction "2_2") (pintype "passive"))
      (node (ref "P2") (pin "1") (pinfunction "1_1") (pintype "passive"))
      (node (ref "P3") (pin "1") (pinfunction "1_1") (pintype "passive"))
      (node (ref "R10") (pin "2") (pinfunction "2_2") (pintype "passive"))
      (node (ref "R2") (pin "2") (pinfunction "2_2") (pintype "passive"))
      (node (ref "R21") (pin "2") (pinfunction "2_2") (pintype "passive"))
      (node (ref "R22") (pin "2") (pinfunction "2_2") (pintype "passive"))
      (node (ref "R5") (pin "1") (pinfunction "1_1") (pintype "passive"))
      (node (ref "R7") (pin "2") (pinfunction "2_2") (pintype "passive"))
      (node (ref "R8") (pin "1") (pinfunction "1_1") (pintype "passive"))
      (node (ref "U1") (pin "1") (pinfunction "VBAT_1") (pintype "power_in"))
      (node (ref "U1") (pin "24") (pinfunction "VDD_1_24") (pintype "power_in"))
      (node (ref "U1") (pin "36") (pinfunction "VDD_2_36") (pintype "power_in"))
      (node (ref "U1") (pin "48") (pinfunction "VDD_3_48") (pintype "power_in"))
      (node (ref "U4") (pin "5") (pinfunction "VOUT_5") (pintype "passive"))
    )
    (net (code "22") (name "GND") (class "Default")
      (node (ref "C1") (pin "1") (pinfunction "1_1") (pintype "passive"))
      (node (ref "C11") (pin "1") (pinfunction "1_1") (pintype "passive"))
      (node (ref "C12") (pin "1") (pinfunction "1_1") (pintype "passive"))
      (node (ref "C25") (pin "1") (pinfunction "1_1") (pintype "passive"))
      (node (ref "C26") (pin "1") (pinfunction "1_1") (pintype "passive"))
      (node (ref "C27") (pin "1") (pinfunction "1_1") (pintype "passive"))
      (node (ref "C28") (pin "1") (pinfunction "1_1") (pintype "passive"))
      (node (ref "C29") (pin "1") (pinfunction "1_1") (pintype "passive"))
      (node (ref "C39") (pin "2") (pinfunction "2_2") (pintype "passive"))
      (node (ref "C4") (pin "1") (pinfunction "1_1") (pintype "passive"))
      (node (ref "C40") (pin "2") (pinfunction "2_2") (pintype "passive"))
      (node (ref "C42") (pin "1") (pinfunction "1_1") (pintype "passive"))
      (node (ref "C44") (pin "1") (pinfunction "1_1") (pintype "passive"))
      (node (ref "C48") (pin "2") (pinfunction "2_2") (pintype "passive"))
      (node (ref "C49") (pin "1") (pinfunction "1_1") (pintype "passive"))
      (node (ref "C50") (pin "2") (pinfunction "2_2") (pintype "passive"))
      (node (ref "C51") (pin "2") (pinfunction "2_2") (pintype "passive"))
      (node (ref "C52") (pin "2") (pinfunction "2_2") (pintype "passive"))
      (node (ref "C54") (pin "1") (pinfunction "1_1") (pintype "passive"))
      (node (ref "C57") (pin "2") (pinfunction "2_2") (pintype "passive"))
      (node (ref "C58") (pin "2") (pinfunction "2_2") (pintype "passive"))
      (node (ref "C59") (pin "2") (pinfunction "2_2") (pintype "passive"))
      (node (ref "C60") (pin "1") (pinfunction "1_1") (pintype "passive"))
      (node (ref "FB3") (pin "1") (pinfunction "1_1") (pintype "passive"))
      (node (ref "FB5") (pin "1") (pinfunction "1_1") (pintype "passive"))
      (node (ref "FB7") (pin "1") (pinfunction "1_1") (pintype "passive"))
      (node (ref "IC1") (pin "1") (pinfunction "A0_1") (pintype "input"))
      (node (ref "IC1") (pin "2") (pinfunction "A1_2") (pintype "input"))
      (node (ref "IC1") (pin "3") (pinfunction "A2_3") (pintype "input"))
      (node (ref "IC1") (pin "4") (pinfunction "GND_4") (pintype "passive"))
      (node (ref "JP3") (pin "1") (pinfunction "1_1") (pintype "passive"))
      (node (ref "LED4") (pin "2") (pinfunction "K_2") (pintype "passive"))
      (node (ref "P1") (pin "1") (pinfunction "1_1") (pintype "passive"))
      (node (ref "P2") (pin "2") (pinfunction "2_2") (pintype "passive"))
      (node (ref "P3") (pin "2") (pinfunction "2_2") (pintype "passive"))
      (node (ref "Q1") (pin "2") (pinfunction "S_2") (pintype "passive"))
      (node (ref "R12") (pin "2") (pinfunction "2_2") (pintype "passive"))
      (node (ref "R13") (pin "2") (pinfunction "2_2") (pintype "passive"))
      (node (ref "R14") (pin "1") (pinfunction "1_1") (pintype "passive"))
      (node (ref "R23") (pin "1") (pinfunction "1_1") (pintype "passive"))
      (node (ref "R3") (pin "2") (pinfunction "2_2") (pintype "passive"))
      (node (ref "R6") (pin "1") (pinfunction "1_1") (pintype "passive"))
      (node (ref "R9") (pin "2") (pinfunction "2_2") (pintype "passive"))
      (node (ref "SW1") (pin "2") (pinfunction "2_2") (pintype "passive"))
      (node (ref "SW2") (pin "2") (pinfunction "2_2") (pintype "passive"))
      (node (ref "SW3") (pin "2") (pinfunction "2_2") (pintype "passive"))
      (node (ref "U1") (pin "23") (pinfunction "VSS_1_23") (pintype "power_in"))
      (node (ref "U1") (pin "35") (pinfunction "VSS_2_35") (pintype "power_in"))
      (node (ref "U1") (pin "47") (pinfunction "VSS_3_47") (pintype "power_in"))
      (node (ref "U3") (pin "3") (pinfunction "VSSA_3") (pintype "passive"))
      (node (ref "U4") (pin "2") (pinfunction "GND_2") (pintype "passive"))
      (node (ref "U5") (pin "2") (pinfunction "GND_2") (pintype "passive"))
      (node (ref "USBC1") (pin "0") (pinfunction "0_0") (pintype "passive"))
      (node (ref "USBC1") (pin "A1") (pinfunction "GND_A1") (pintype "passive"))
      (node (ref "USBC1") (pin "A12") (pinfunction "GND_A12") (pintype "passive"))
      (node (ref "USBC1") (pin "B1") (pinfunction "GND_B1") (pintype "passive"))
      (node (ref "USBC1") (pin "B12") (pinfunction "GND_B12") (pintype "passive"))
    )
    (net (code "23") (name "GNDA") (class "Default")
      (node (ref "C37") (pin "1") (pinfunction "1_1") (pintype "passive"))
      (node (ref "C38") (pin "1") (pinfunction "1_1") (pintype "passive"))
      (node (ref "C43") (pin "1") (pinfunction "1_1") (pintype "passive"))
      (node (ref "C45") (pin "1") (pinfunction "1_1") (pintype "passive"))
      (node (ref "C46") (pin "1") (pinfunction "1_1") (pintype "passive"))
      (node (ref "C47") (pin "1") (pinfunction "1_1") (pintype "passive"))
      (node (ref "C55") (pin "1") (pinfunction "1_1") (pintype "passive"))
      (node (ref "C56") (pin "1") (pinfunction "1_1") (pintype "passive"))
      (node (ref "FB7") (pin "2") (pinfunction "2_2") (pintype "passive"))
      (node (ref "U3") (pin "27") (pinfunction "GND_HP_27") (pintype "passive"))
      (node (ref "U3") (pin "36") (pinfunction "AVSS_36") (pintype "passive"))
      (node (ref "U3") (pin "44") (pinfunction "GNDCP_44") (pintype "passive"))
    )
    (net (code "24") (name "GNDRF") (class "Default")
      (node (ref "BK1") (pin "33") (pinfunction "33_33") (pintype "passive"))
      (node (ref "C17") (pin "2") (pinfunction "2_2") (pintype "passive"))
      (node (ref "C18") (pin "2") (pinfunction "2_2") (pintype "passive"))
      (node (ref "C19") (pin "2") (pinfunction "2_2") (pintype "passive"))
      (node (ref "C2") (pin "1") (pinfunction "1_1") (pintype "passive"))
      (node (ref "C20") (pin "2") (pinfunction "2_2") (pintype "passive"))
      (node (ref "C21") (pin "2") (pinfunction "2_2") (pintype "passive"))
      (node (ref "C23") (pin "1") (pinfunction "1_1") (pintype "passive"))
      (node (ref "C24") (pin "2") (pinfunction "2_2") (pintype "passive"))
      (node (ref "C3") (pin "1") (pinfunction "1_1") (pintype "passive"))
      (node (ref "C30") (pin "1") (pinfunction "1_1") (pintype "passive"))
      (node (ref "C31") (pin "1") (pinfunction "1_1") (pintype "passive"))
      (node (ref "C32") (pin "1") (pinfunction "1_1") (pintype "passive"))
      (node (ref "C33") (pin "2") (pinfunction "2_2") (pintype "passive"))
      (node (ref "C34") (pin "2") (pinfunction "2_2") (pintype "passive"))
      (node (ref "C35") (pin "2") (pinfunction "2_2") (pintype "passive"))
      (node (ref "C36") (pin "1") (pinfunction "1_1") (pintype "passive"))
      (node (ref "C5") (pin "1") (pinfunction "1_1") (pintype "passive"))
      (node (ref "C6") (pin "1") (pinfunction "1_1") (pintype "passive"))
      (node (ref "C7") (pin "1") (pinfunction "1_1") (pintype "passive"))
      (node (ref "C8") (pin "1") (pinfunction "1_1") (pintype "passive"))
      (node (ref "FB5") (pin "2") (pinfunction "2_2") (pintype "passive"))
      (node (ref "JP1") (pin "2") (pinfunction "GND_2") (pintype "passive"))
      (node (ref "JP1") (pin "3") (pinfunction "GND_3") (pintype "passive"))
      (node (ref "JP2") (pin "2") (pinfunction "GND_2") (pintype "passive"))
      (node (ref "JP2") (pin "3") (pinfunction "GND_3") (pintype "passive"))
      (node (ref "L5") (pin "1") (pinfunction "1_1") (pintype "passive"))
      (node (ref "R11") (pin "1") (pinfunction "1_1") (pintype "passive"))
      (node (ref "U2") (pin "2") (pinfunction "GND_2") (pintype "passive"))
    )
    (net (code "25") (name "IR1.8V") (class "Default")
      (node (ref "C53") (pin "1") (pinfunction "1_1") (pintype "passive"))
      (node (ref "C58") (pin "1") (pinfunction "1_1") (pintype "passive"))
      (node (ref "C59") (pin "1") (pinfunction "1_1") (pintype "passive"))
      (node (ref "L6") (pin "2") (pinfunction "2_2") (pintype "passive"))
      (node (ref "R1") (pin "2") (pinfunction "2_2") (pintype "passive"))
      (node (ref "R20") (pin "2") (pinfunction "2_2") (pintype "passive"))
    )
    (net (code "26") (name "Net-(BK1-EXCN)") (class "Default")
      (node (ref "BK1") (pin "12") (pinfunction "EXCN_12") (pintype "passive"))
      (node (ref "C22") (pin "2") (pinfunction "2_2") (pintype "passive"))
    )
    (net (code "27") (name "Net-(BK1-EXCP)") (class "Default")
      (node (ref "BK1") (pin "11") (pinfunction "EXCP_11") (pintype "passive"))
      (node (ref "C22") (pin "1") (pinfunction "1_1") (pintype "passive"))
    )
    (net (code "28") (name "Net-(BK1-TXON)") (class "Default")
      (node (ref "BK1") (pin "9") (pinfunction "TXON_9") (pintype "passive"))
      (node (ref "C10") (pin "1") (pinfunction "1_1") (pintype "passive"))
      (node (ref "L1") (pin "1") (pinfunction "1_1") (pintype "passive"))
    )
    (net (code "29") (name "Net-(BK1-TXOP)") (class "Default")
      (node (ref "BK1") (pin "10") (pinfunction "TXOP_10") (pintype "passive"))
      (node (ref "C16") (pin "1") (pinfunction "1_1") (pintype "passive"))
      (node (ref "L2") (pin "1") (pinfunction "1_1") (pintype "passive"))
    )
    (net (code "30") (name "Net-(BK1-VCCTX)") (class "Default")
      (node (ref "BK1") (pin "7") (pinfunction "VCCTX_7") (pintype "passive"))
      (node (ref "FB1") (pin "2") (pinfunction "2_2") (pintype "passive"))
    )
    (net (code "31") (name "Net-(BK1-VDDDIG)") (class "Default")
      (node (ref "BK1") (pin "17") (pinfunction "VDDDIG_17") (pintype "passive"))
      (node (ref "C31") (pin "2") (pinfunction "2_2") (pintype "passive"))
    )
    (net (code "32") (name "Net-(BK1-VDDVCO)") (class "Default")
      (node (ref "BK1") (pin "1") (pinfunction "VDDVCO_1") (pintype "passive"))
      (node (ref "C7") (pin "2") (pinfunction "2_2") (pintype "passive"))
    )
    (net (code "33") (name "Net-(BK1-XI)") (class "Default")
      (node (ref "BK1") (pin "31") (pinfunction "XI_31") (pintype "passive"))
      (node (ref "C20") (pin "1") (pinfunction "1_1") (pintype "passive"))
      (node (ref "Y1") (pin "2") (pinfunction "GND_2") (pintype "passive"))
    )
    (net (code "34") (name "Net-(BK1-XO)") (class "Default")
      (node (ref "BK1") (pin "30") (pinfunction "XO_30") (pintype "passive"))
      (node (ref "C21") (pin "1") (pinfunction "1_1") (pintype "passive"))
    )
    (net (code "35") (name "Net-(C2-Pad2)") (class "Default")
      (node (ref "C2") (pin "2") (pinfunction "2_2") (pintype "passive"))
      (node (ref "C3") (pin "2") (pinfunction "2_2") (pintype "passive"))
      (node (ref "FB1") (pin "1") (pinfunction "1_1") (pintype "passive"))
      (node (ref "L1") (pin "2") (pinfunction "2_2") (pintype "passive"))
      (node (ref "L2") (pin "2") (pinfunction "2_2") (pintype "passive"))
    )
    (net (code "36") (name "Net-(C10-Pad2)") (class "Default")
      (node (ref "C10") (pin "2") (pinfunction "2_2") (pintype "passive"))
      (node (ref "C8") (pin "2") (pinfunction "2_2") (pintype "passive"))
      (node (ref "L4") (pin "2") (pinfunction "2_2") (pintype "passive"))
    )
    (net (code "37") (name "Net-(C15-Pad1)") (class "Default")
      (node (ref "C15") (pin "1") (pinfunction "1_1") (pintype "passive"))
      (node (ref "C16") (pin "2") (pinfunction "2_2") (pintype "passive"))
      (node (ref "L5") (pin "2") (pinfunction "2_2") (pintype "passive"))
    )
    (net (code "38") (name "Net-(C15-Pad2)") (class "Default")
      (node (ref "C15") (pin "2") (pinfunction "2_2") (pintype "passive"))
      (node (ref "C9") (pin "1") (pinfunction "1_1") (pintype "passive"))
      (node (ref "L4") (pin "1") (pinfunction "1_1") (pintype "passive"))
    )
    (net (code "39") (name "Net-(IC1-SCL)") (class "Default")
      (node (ref "IC1") (pin "6") (pinfunction "SCL_6") (pintype "input"))
      (node (ref "R21") (pin "1") (pinfunction "1_1") (pintype "passive"))
      (node (ref "U3") (pin "18") (pinfunction "I2C_SCL_18") (pintype "passive"))
    )
    (net (code "40") (name "Net-(IC1-SDA)") (class "Default")
      (node (ref "IC1") (pin "5") (pinfunction "SDA_5") (pintype "bidirectional"))
      (node (ref "R22") (pin "1") (pinfunction "1_1") (pintype "passive"))
      (node (ref "U3") (pin "19") (pinfunction "I2C_SDA_19") (pintype "passive"))
    )
    (net (code "41") (name "Net-(JP1-ANT)") (class "Default")
      (node (ref "C18") (pin "1") (pinfunction "1_1") (pintype "passive"))
      (node (ref "C9") (pin "2") (pinfunction "2_2") (pintype "passive"))
      (node (ref "JP1") (pin "1") (pinfunction "ANT_1") (pintype "passive"))
      (node (ref "L3") (pin "2") (pinfunction "2_2") (pintype "passive"))
    )
    (net (code "42") (name "Net-(JP2-ANT)") (class "Default")
      (node (ref "C17") (pin "1") (pinfunction "1_1") (pintype "passive"))
      (node (ref "JP2") (pin "1") (pinfunction "ANT_1") (pintype "passive"))
      (node (ref "L3") (pin "1") (pinfunction "1_1") (pintype "passive"))
    )
    (net (code "43") (name "Net-(LED1-A)") (class "Default")
      (node (ref "LED1") (pin "1") (pinfunction "A_1") (pintype "passive"))
      (node (ref "R1") (pin "1") (pinfunction "1_1") (pintype "passive"))
    )
    (net (code "44") (name "Net-(LED1-K)") (class "Default")
      (node (ref "LED1") (pin "2") (pinfunction "K_2") (pintype "passive"))
      (node (ref "Q1") (pin "3") (pinfunction "D_3") (pintype "passive"))
    )
    (net (code "45") (name "Net-(LED2-A)") (class "Default")
      (node (ref "LED2") (pin "1") (pinfunction "A_1") (pintype "passive"))
      (node (ref "R2") (pin "1") (pinfunction "1_1") (pintype "passive"))
    )
    (net (code "46") (name "Net-(LED3-A)") (class "Default")
      (node (ref "LED3") (pin "1") (pinfunction "A_1") (pintype "passive"))
      (node (ref "R7") (pin "1") (pinfunction "1_1") (pintype "passive"))
    )
    (net (code "47") (name "Net-(LED4-A)") (class "Default")
      (node (ref "LED4") (pin "1") (pinfunction "A_1") (pintype "passive"))
      (node (ref "R19") (pin "1") (pinfunction "1_1") (pintype "passive"))
    )
    (net (code "48") (name "Net-(Q1-G)") (class "Default")
      (node (ref "Q1") (pin "1") (pinfunction "G_1") (pintype "passive"))
      (node (ref "R4") (pin "1") (pinfunction "1_1") (pintype "passive"))
      (node (ref "R6") (pin "2") (pinfunction "2_2") (pintype "passive"))
    )
    (net (code "49") (name "Net-(U1A-BOOT0)") (class "Default")
      (node (ref "R9") (pin "1") (pinfunction "1_1") (pintype "passive"))
      (node (ref "U1") (pin "44") (pinfunction "BOOT0_44") (pintype "input"))
    )
    (net (code "50") (name "Net-(U1A-PA3)") (class "Default")
      (node (ref "R4") (pin "2") (pinfunction "2_2") (pintype "passive"))
      (node (ref "U1") (pin "13") (pinfunction "PA3_13") (pintype "bidirectional"))
    )
    (net (code "51") (name "Net-(U1A-PB0)") (class "Default")
      (node (ref "C1") (pin "2") (pinfunction "2_2") (pintype "passive"))
      (node (ref "SW1") (pin "1") (pinfunction "1_1") (pintype "passive"))
      (node (ref "U1") (pin "18") (pinfunction "PB0_18") (pintype "bidirectional"))
    )
    (net (code "52") (name "Net-(U1A-PB1)") (class "Default")
      (node (ref "C4") (pin "2") (pinfunction "2_2") (pintype "passive"))
      (node (ref "SW2") (pin "1") (pinfunction "1_1") (pintype "passive"))
      (node (ref "U1") (pin "19") (pinfunction "PB1_19") (pintype "bidirectional"))
    )
    (net (code "53") (name "Net-(U1A-PB2)") (class "Default")
      (node (ref "R3") (pin "1") (pinfunction "1_1") (pintype "passive"))
      (node (ref "U1") (pin "20") (pinfunction "PB2_20") (pintype "bidirectional"))
    )
    (net (code "54") (name "Net-(U1A-PD0-OSC_IN)") (class "Default")
      (node (ref "C25") (pin "2") (pinfunction "2_2") (pintype "passive"))
      (node (ref "U1") (pin "5") (pinfunction "PD0-OSC_IN_5") (pintype "bidirectional"))
      (node (ref "Y2") (pin "2") (pinfunction "OSC2_2") (pintype "passive"))
    )
    (net (code "55") (name "Net-(U1A-PD1)") (class "Default")
      (node (ref "C29") (pin "2") (pinfunction "2_2") (pintype "passive"))
      (node (ref "U1") (pin "6") (pinfunction "PD1_6") (pintype "bidirectional"))
      (node (ref "Y2") (pin "1") (pinfunction "OSC1_1") (pintype "passive"))
    )
    (net (code "56") (name "Net-(U3-CFLYN)") (class "Default")
      (node (ref "C41") (pin "1") (pinfunction "1_1") (pintype "passive"))
      (node (ref "U3") (pin "43") (pinfunction "CFLYN_43") (pintype "passive"))
    )
    (net (code "57") (name "Net-(U3-CFLYP)") (class "Default")
      (node (ref "C41") (pin "2") (pinfunction "2_2") (pintype "passive"))
      (node (ref "U3") (pin "45") (pinfunction "CFLYP_45") (pintype "passive"))
    )
    (net (code "58") (name "Net-(U3-HPVDD)") (class "Default")
      (node (ref "C45") (pin "2") (pinfunction "2_2") (pintype "passive"))
      (node (ref "U3") (pin "40") (pinfunction "HPVDD_40") (pintype "passive"))
      (node (ref "U3") (pin "41") (pinfunction "VCPP_41") (pintype "passive"))
    )
    (net (code "59") (name "Net-(U3-HPVSS)") (class "Default")
      (node (ref "C43") (pin "2") (pinfunction "2_2") (pintype "passive"))
      (node (ref "U3") (pin "37") (pinfunction "HPVSS_37") (pintype "passive"))
      (node (ref "U3") (pin "42") (pinfunction "VCPN_42") (pintype "passive"))
    )
    (net (code "60") (name "Net-(U3-LEDO)") (class "Default")
      (node (ref "R19") (pin "2") (pinfunction "2_2") (pintype "passive"))
      (node (ref "U3") (pin "8") (pinfunction "LEDO_8") (pintype "passive"))
    )
    (net (code "61") (name "Net-(U3-TEST)") (class "Default")
      (node (ref "R13") (pin "1") (pinfunction "1_1") (pintype "passive"))
      (node (ref "U3") (pin "47") (pinfunction "TEST_47") (pintype "passive"))
    )
    (net (code "62") (name "Net-(U3-V12)") (class "Default")
      (node (ref "C44") (pin "2") (pinfunction "2_2") (pintype "passive"))
      (node (ref "U3") (pin "4") (pinfunction "V12_4") (pintype "passive"))
    )
    (net (code "63") (name "Net-(U3-VMID)") (class "Default")
      (node (ref "C46") (pin "2") (pinfunction "2_2") (pintype "passive"))
      (node (ref "C47") (pin "2") (pinfunction "2_2") (pintype "passive"))
      (node (ref "U3") (pin "35") (pinfunction "VMID_35") (pintype "passive"))
    )
    (net (code "64") (name "Net-(U4-EN)") (class "Default")
      (node (ref "R15") (pin "1") (pinfunction "1_1") (pintype "passive"))
      (node (ref "U4") (pin "3") (pinfunction "EN_3") (pintype "passive"))
    )
    (net (code "65") (name "Net-(U5C-FB)") (class "Default")
      (node (ref "C53") (pin "2") (pinfunction "2_2") (pintype "passive"))
      (node (ref "R20") (pin "1") (pinfunction "1_1") (pintype "passive"))
      (node (ref "R23") (pin "2") (pinfunction "2_2") (pintype "passive"))
      (node (ref "U5") (pin "5") (pinfunction "FB_5") (pintype "passive"))
    )
    (net (code "66") (name "Net-(U5C-LX)") (class "Default")
      (node (ref "L6") (pin "1") (pinfunction "1_1") (pintype "passive"))
      (node (ref "U5") (pin "3") (pinfunction "LX_3") (pintype "passive"))
    )
    (net (code "67") (name "Net-(USBC1-CC1)") (class "Default")
      (node (ref "R14") (pin "2") (pinfunction "2_2") (pintype "passive"))
      (node (ref "USBC1") (pin "A5") (pinfunction "CC1_A5") (pintype "passive"))
    )
    (net (code "68") (name "Net-(USBC1-CC2)") (class "Default")
      (node (ref "R12") (pin "1") (pinfunction "1_1") (pintype "passive"))
      (node (ref "USBC1") (pin "B5") (pinfunction "CC2_B5") (pintype "passive"))
    )
    (net (code "69") (name "RF3V3") (class "Default")
      (node (ref "BK1") (pin "13") (pinfunction "VCCAUD_13") (pintype "passive"))
      (node (ref "BK1") (pin "16") (pinfunction "VCCDIG_16") (pintype "passive"))
      (node (ref "BK1") (pin "2") (pinfunction "VCCVCO_2") (pintype "passive"))
      (node (ref "BK1") (pin "24") (pinfunction "VCCIF_24") (pintype "passive"))
      (node (ref "BK1") (pin "28") (pinfunction "VCCDVCO_28") (pintype "passive"))
      (node (ref "BK1") (pin "29") (pinfunction "VCCXTAL_29") (pintype "passive"))
      (node (ref "BK1") (pin "32") (pinfunction "VCCPLL_32") (pintype "passive"))
      (node (ref "BK1") (pin "4") (pinfunction "VCCB_4") (pintype "passive"))
      (node (ref "BK1") (pin "8") (pinfunction "VCCPA_8") (pintype "passive"))
      (node (ref "C19") (pin "1") (pinfunction "1_1") (pintype "passive"))
      (node (ref "C23") (pin "2") (pinfunction "2_2") (pintype "passive"))
      (node (ref "C24") (pin "1") (pinfunction "1_1") (pintype "passive"))
      (node (ref "C30") (pin "2") (pinfunction "2_2") (pintype "passive"))
      (node (ref "C32") (pin "2") (pinfunction "2_2") (pintype "passive"))
      (node (ref "C34") (pin "1") (pinfunction "1_1") (pintype "passive"))
      (node (ref "C35") (pin "1") (pinfunction "1_1") (pintype "passive"))
      (node (ref "C36") (pin "2") (pinfunction "2_2") (pintype "passive"))
      (node (ref "C5") (pin "2") (pinfunction "2_2") (pintype "passive"))
      (node (ref "C6") (pin "2") (pinfunction "2_2") (pintype "passive"))
      (node (ref "U2") (pin "5") (pinfunction "VOUT_5") (pintype "passive"))
    )
    (net (code "70") (name "USB_5V") (class "Default")
      (node (ref "C26") (pin "2") (pinfunction "2_2") (pintype "passive"))
      (node (ref "C33") (pin "1") (pinfunction "1_1") (pintype "passive"))
      (node (ref "C50") (pin "1") (pinfunction "1_1") (pintype "passive"))
      (node (ref "C51") (pin "1") (pinfunction "1_1") (pintype "passive"))
      (node (ref "C57") (pin "1") (pinfunction "1_1") (pintype "passive"))
      (node (ref "FB4") (pin "1") (pinfunction "1_1") (pintype "passive"))
      (node (ref "R15") (pin "2") (pinfunction "2_2") (pintype "passive"))
      (node (ref "U2") (pin "1") (pinfunction "VIN_1") (pintype "passive"))
      (node (ref "U4") (pin "1") (pinfunction "VIN_1") (pintype "passive"))
      (node (ref "U5") (pin "4") (pinfunction "VIN_4") (pintype "passive"))
    )
    (net (code "71") (name "VBUS") (class "Default")
      (node (ref "C27") (pin "2") (pinfunction "2_2") (pintype "passive"))
      (node (ref "C28") (pin "2") (pinfunction "2_2") (pintype "passive"))
      (node (ref "FB4") (pin "2") (pinfunction "2_2") (pintype "passive"))
      (node (ref "U3") (pin "1") (pinfunction "VBUS_1") (pintype "passive"))
      (node (ref "USBC1") (pin "A4") (pinfunction "VBUS_A4") (pintype "passive"))
      (node (ref "USBC1") (pin "A9") (pinfunction "VBUS_A9") (pintype "passive"))
      (node (ref "USBC1") (pin "B4") (pinfunction "VBUS_B4") (pintype "passive"))
      (node (ref "USBC1") (pin "B9") (pinfunction "VBUS_B9") (pintype "passive"))
    )
    (net (code "72") (name "VDDA") (class "Default")
      (node (ref "C13") (pin "2") (pinfunction "2_2") (pintype "passive"))
      (node (ref "C14") (pin "2") (pinfunction "2_2") (pintype "passive"))
      (node (ref "FB2") (pin "2") (pinfunction "2_2") (pintype "passive"))
      (node (ref "U1") (pin "9") (pinfunction "VDDA_9") (pintype "power_in"))
    )
    (net (code "73") (name "VSSA") (class "Default")
      (node (ref "C13") (pin "1") (pinfunction "1_1") (pintype "passive"))
      (node (ref "C14") (pin "1") (pinfunction "1_1") (pintype "passive"))
      (node (ref "FB3") (pin "2") (pinfunction "2_2") (pintype "passive"))
      (node (ref "U1") (pin "8") (pinfunction "VSSA_8") (pintype "power_in"))
    )
    (net (code "74") (name "unconnected-(BK1-GPIO2-Pad20)") (class "Default")
      (node (ref "BK1") (pin "20") (pinfunction "GPIO2_20") (pintype "passive"))
    )
    (net (code "75") (name "unconnected-(BK1-GPIO4-Pad25)") (class "Default")
      (node (ref "BK1") (pin "25") (pinfunction "GPIO4_25") (pintype "passive+no_connect"))
    )
    (net (code "76") (name "unconnected-(BK1-IRQ-Pad27)") (class "Default")
      (node (ref "BK1") (pin "27") (pinfunction "IRQ_27") (pintype "passive+no_connect"))
    )
    (net (code "77") (name "unconnected-(BK1-MICN-Pad14)") (class "Default")
      (node (ref "BK1") (pin "14") (pinfunction "MICN_14") (pintype "passive+no_connect"))
    )
    (net (code "78") (name "unconnected-(BK1-MICP-Pad15)") (class "Default")
      (node (ref "BK1") (pin "15") (pinfunction "MICP_15") (pintype "passive+no_connect"))
    )
    (net (code "79") (name "unconnected-(BK1-NC-Pad5)") (class "Default")
      (node (ref "BK1") (pin "5") (pinfunction "NC_5") (pintype "passive"))
    )
    (net (code "80") (name "unconnected-(BK1-NC-Pad6)") (class "Default")
      (node (ref "BK1") (pin "6") (pinfunction "NC_6") (pintype "passive"))
    )
    (net (code "81") (name "unconnected-(BK1-XO2-Pad23)") (class "Default")
      (node (ref "BK1") (pin "23") (pinfunction "XO2_23") (pintype "passive"))
    )
    (net (code "82") (name "unconnected-(IC1-WP-Pad7)") (class "Default")
      (node (ref "IC1") (pin "7") (pinfunction "WP_7") (pintype "passive+no_connect"))
    )
    (net (code "83") (name "unconnected-(U1A-PA4-Pad14)") (class "Default")
      (node (ref "U1") (pin "14") (pinfunction "PA4_14") (pintype "bidirectional"))
    )
    (net (code "84") (name "unconnected-(U1A-PA7-Pad17)") (class "Default")
      (node (ref "U1") (pin "17") (pinfunction "PA7_17") (pintype "bidirectional"))
    )
    (net (code "85") (name "unconnected-(U1A-PA8-Pad29)") (class "Default")
      (node (ref "U1") (pin "29") (pinfunction "PA8_29") (pintype "bidirectional"))
    )
    (net (code "86") (name "unconnected-(U1A-PA9-Pad30)") (class "Default")
      (node (ref "U1") (pin "30") (pinfunction "PA9_30") (pintype "bidirectional"))
    )
    (net (code "87") (name "unconnected-(U1A-PA10-Pad31)") (class "Default")
      (node (ref "U1") (pin "31") (pinfunction "PA10_31") (pintype "bidirectional"))
    )
    (net (code "88") (name "unconnected-(U1A-PA11-Pad32)") (class "Default")
      (node (ref "U1") (pin "32") (pinfunction "PA11_32") (pintype "bidirectional"))
    )
    (net (code "89") (name "unconnected-(U1A-PA15-Pad38)") (class "Default")
      (node (ref "U1") (pin "38") (pinfunction "PA15_38") (pintype "bidirectional"))
    )
    (net (code "90") (name "unconnected-(U1A-PB3-Pad39)") (class "Default")
      (node (ref "U1") (pin "39") (pinfunction "PB3_39") (pintype "bidirectional"))
    )
    (net (code "91") (name "unconnected-(U1A-PB4-Pad40)") (class "Default")
      (node (ref "U1") (pin "40") (pinfunction "PB4_40") (pintype "bidirectional"))
    )
    (net (code "92") (name "unconnected-(U1A-PB5-Pad41)") (class "Default")
      (node (ref "U1") (pin "41") (pinfunction "PB5_41") (pintype "bidirectional"))
    )
    (net (code "93") (name "unconnected-(U1A-PB8-Pad45)") (class "Default")
      (node (ref "U1") (pin "45") (pinfunction "PB8_45") (pintype "bidirectional"))
    )
    (net (code "94") (name "unconnected-(U1A-PB9-Pad46)") (class "Default")
      (node (ref "U1") (pin "46") (pinfunction "PB9_46") (pintype "bidirectional"))
    )
    (net (code "95") (name "unconnected-(U1A-PB10-Pad21)") (class "Default")
      (node (ref "U1") (pin "21") (pinfunction "PB10_21") (pintype "bidirectional"))
    )
    (net (code "96") (name "unconnected-(U1A-PB11-Pad22)") (class "Default")
      (node (ref "U1") (pin "22") (pinfunction "PB11_22") (pintype "bidirectional"))
    )
    (net (code "97") (name "unconnected-(U1A-PB12-Pad25)") (class "Default")
      (node (ref "U1") (pin "25") (pinfunction "PB12_25") (pintype "bidirectional"))
    )
    (net (code "98") (name "unconnected-(U1A-PB13-Pad26)") (class "Default")
      (node (ref "U1") (pin "26") (pinfunction "PB13_26") (pintype "bidirectional"))
    )
    (net (code "99") (name "unconnected-(U1A-PB14-Pad27)") (class "Default")
      (node (ref "U1") (pin "27") (pinfunction "PB14_27") (pintype "bidirectional"))
    )
    (net (code "100") (name "unconnected-(U1A-PB15-Pad28)") (class "Default")
      (node (ref "U1") (pin "28") (pinfunction "PB15_28") (pintype "bidirectional"))
    )
    (net (code "101") (name "unconnected-(U1A-PC13-TAMPER-RTC-Pad2)") (class "Default")
      (node (ref "U1") (pin "2") (pinfunction "PC13-TAMPER-RTC_2") (pintype "bidirectional"))
    )
    (net (code "102") (name "unconnected-(U1A-PC14-OSC32_IN-Pad3)") (class "Default")
      (node (ref "U1") (pin "3") (pinfunction "PC14-OSC32_IN_3") (pintype "bidirectional"))
    )
    (net (code "103") (name "unconnected-(U1A-PC15-OSC32_OUT-Pad4)") (class "Default")
      (node (ref "U1") (pin "4") (pinfunction "PC15-OSC32_OUT_4") (pintype "bidirectional"))
    )
    (net (code "104") (name "unconnected-(U2-NC-Pad4)") (class "Default")
      (node (ref "U2") (pin "4") (pinfunction "NC_4") (pintype "passive+no_connect"))
    )
    (net (code "105") (name "unconnected-(U3-EQ3D_LED-Pad48)") (class "Default")
      (node (ref "U3") (pin "48") (pinfunction "EQ3D_LED_48") (pintype "passive+no_connect"))
    )
    (net (code "106") (name "unconnected-(U3-INSEL-Pad9)") (class "Default")
      (node (ref "U3") (pin "9") (pinfunction "INSEL_9") (pintype "passive"))
    )
    (net (code "107") (name "unconnected-(U3-KEY_RENC_INV-Pad7)") (class "Default")
      (node (ref "U3") (pin "7") (pinfunction "KEY_RENC_INV_7") (pintype "passive+no_connect"))
    )
    (net (code "108") (name "unconnected-(U3-LHPOUT-Pad39)") (class "Default")
      (node (ref "U3") (pin "39") (pinfunction "LHPOUT_39") (pintype "passive+no_connect"))
    )
    (net (code "109") (name "unconnected-(U3-MIC1-Pad29)") (class "Default")
      (node (ref "U3") (pin "29") (pinfunction "MIC1_29") (pintype "passive+no_connect"))
    )
    (net (code "110") (name "unconnected-(U3-MIC1N-Pad31)") (class "Default")
      (node (ref "U3") (pin "31") (pinfunction "MIC1N_31") (pintype "passive+no_connect"))
    )
    (net (code "111") (name "unconnected-(U3-MIC1P-Pad32)") (class "Default")
      (node (ref "U3") (pin "32") (pinfunction "MIC1P_32") (pintype "passive+no_connect"))
    )
    (net (code "112") (name "unconnected-(U3-MIC2P-Pad33)") (class "Default")
      (node (ref "U3") (pin "33") (pinfunction "MIC2P_33") (pintype "passive+no_connect"))
    )
    (net (code "113") (name "unconnected-(U3-MICBIAS-Pad30)") (class "Default")
      (node (ref "U3") (pin "30") (pinfunction "MICBIAS_30") (pintype "passive+no_connect"))
    )
    (net (code "114") (name "unconnected-(U3-MSEL-Pad10)") (class "Default")
      (node (ref "U3") (pin "10") (pinfunction "MSEL_10") (pintype "passive+no_connect"))
    )
    (net (code "115") (name "unconnected-(U3-NEXT_TRACK-Pad20)") (class "Default")
      (node (ref "U3") (pin "20") (pinfunction "NEXT_TRACK_20") (pintype "passive+no_connect"))
    )
    (net (code "116") (name "unconnected-(U3-PALY_PAUSE-Pad22)") (class "Default")
      (node (ref "U3") (pin "22") (pinfunction "PALY_PAUSE_22") (pintype "passive+no_connect"))
    )
    (net (code "117") (name "unconnected-(U3-PLAY_EN-Pad16)") (class "Default")
      (node (ref "U3") (pin "16") (pinfunction "PLAY_EN_16") (pintype "passive+no_connect"))
    )
    (net (code "118") (name "unconnected-(U3-PRE_TACK-Pad21)") (class "Default")
      (node (ref "U3") (pin "21") (pinfunction "PRE_TACK_21") (pintype "passive+no_connect"))
    )
    (net (code "119") (name "unconnected-(U3-REC_EN-Pad17)") (class "Default")
      (node (ref "U3") (pin "17") (pinfunction "REC_EN_17") (pintype "passive+no_connect"))
    )
    (net (code "120") (name "unconnected-(U3-RHPOUT-Pad38)") (class "Default")
      (node (ref "U3") (pin "38") (pinfunction "RHPOUT_38") (pintype "passive+no_connect"))
    )
    (net (code "121") (name "unconnected-(U3-RING2-Pad28)") (class "Default")
      (node (ref "U3") (pin "28") (pinfunction "RING2_28") (pintype "passive+no_connect"))
    )
    (net (code "122") (name "unconnected-(U3-SLEEVE-Pad26)") (class "Default")
      (node (ref "U3") (pin "26") (pinfunction "SLEEVE_26") (pintype "passive+no_connect"))
    )
    (net (code "123") (name "unconnected-(U3-STEREO_MIC-Pad13)") (class "Default")
      (node (ref "U3") (pin "13") (pinfunction "STEREO_MIC_13") (pintype "passive+no_connect"))
    )
    (net (code "124") (name "unconnected-(U3-STOP-Pad24)") (class "Default")
      (node (ref "U3") (pin "24") (pinfunction "STOP_24") (pintype "passive+no_connect"))
    )
    (net (code "125") (name "unconnected-(U3-VOLDN-Pad15)") (class "Default")
      (node (ref "U3") (pin "15") (pinfunction "VOLDN_15") (pintype "passive+no_connect"))
    )
    (net (code "126") (name "unconnected-(U3-VP_MUTE-Pad25)") (class "Default")
      (node (ref "U3") (pin "25") (pinfunction "VP_MUTE_25") (pintype "passive+no_connect"))
    )
    (net (code "127") (name "unconnected-(U3-VR_MUTE-Pad23)") (class "Default")
      (node (ref "U3") (pin "23") (pinfunction "VR_MUTE_23") (pintype "passive+no_connect"))
    )
    (net (code "128") (name "unconnected-(U4-NC-Pad4)") (class "Default")
      (node (ref "U4") (pin "4") (pinfunction "NC_4") (pintype "passive+no_connect"))
    )
    (net (code "129") (name "unconnected-(USBC1-SBU1-PadA8)") (class "Default")
      (node (ref "USBC1") (pin "A8") (pinfunction "SBU1_A8") (pintype "passive"))
    )
    (net (code "130") (name "unconnected-(USBC1-SBU2-PadB8)") (class "Default")
      (node (ref "USBC1") (pin "B8") (pinfunction "SBU2_B8") (pintype "passive"))
    )
    (net (code "131") (name "unconnected-(Y1-NC-Pad1)") (class "Default")
      (node (ref "Y1") (pin "1") (pinfunction "NC_1") (pintype "passive"))
    )
    (net (code "132") (name "unconnected-(Y1-OUT-Pad3)") (class "Default")
      (node (ref "Y1") (pin "3") (pinfunction "OUT_3") (pintype "passive"))
    )
    (net (code "133") (name "unconnected-(Y1-VCC-Pad4)") (class "Default")
      (node (ref "Y1") (pin "4") (pinfunction "VCC_4") (pintype "passive"))
    )
  )
)
